# mippe_32u4.net
KiCad netlist of a schematic drawn in EAGLE
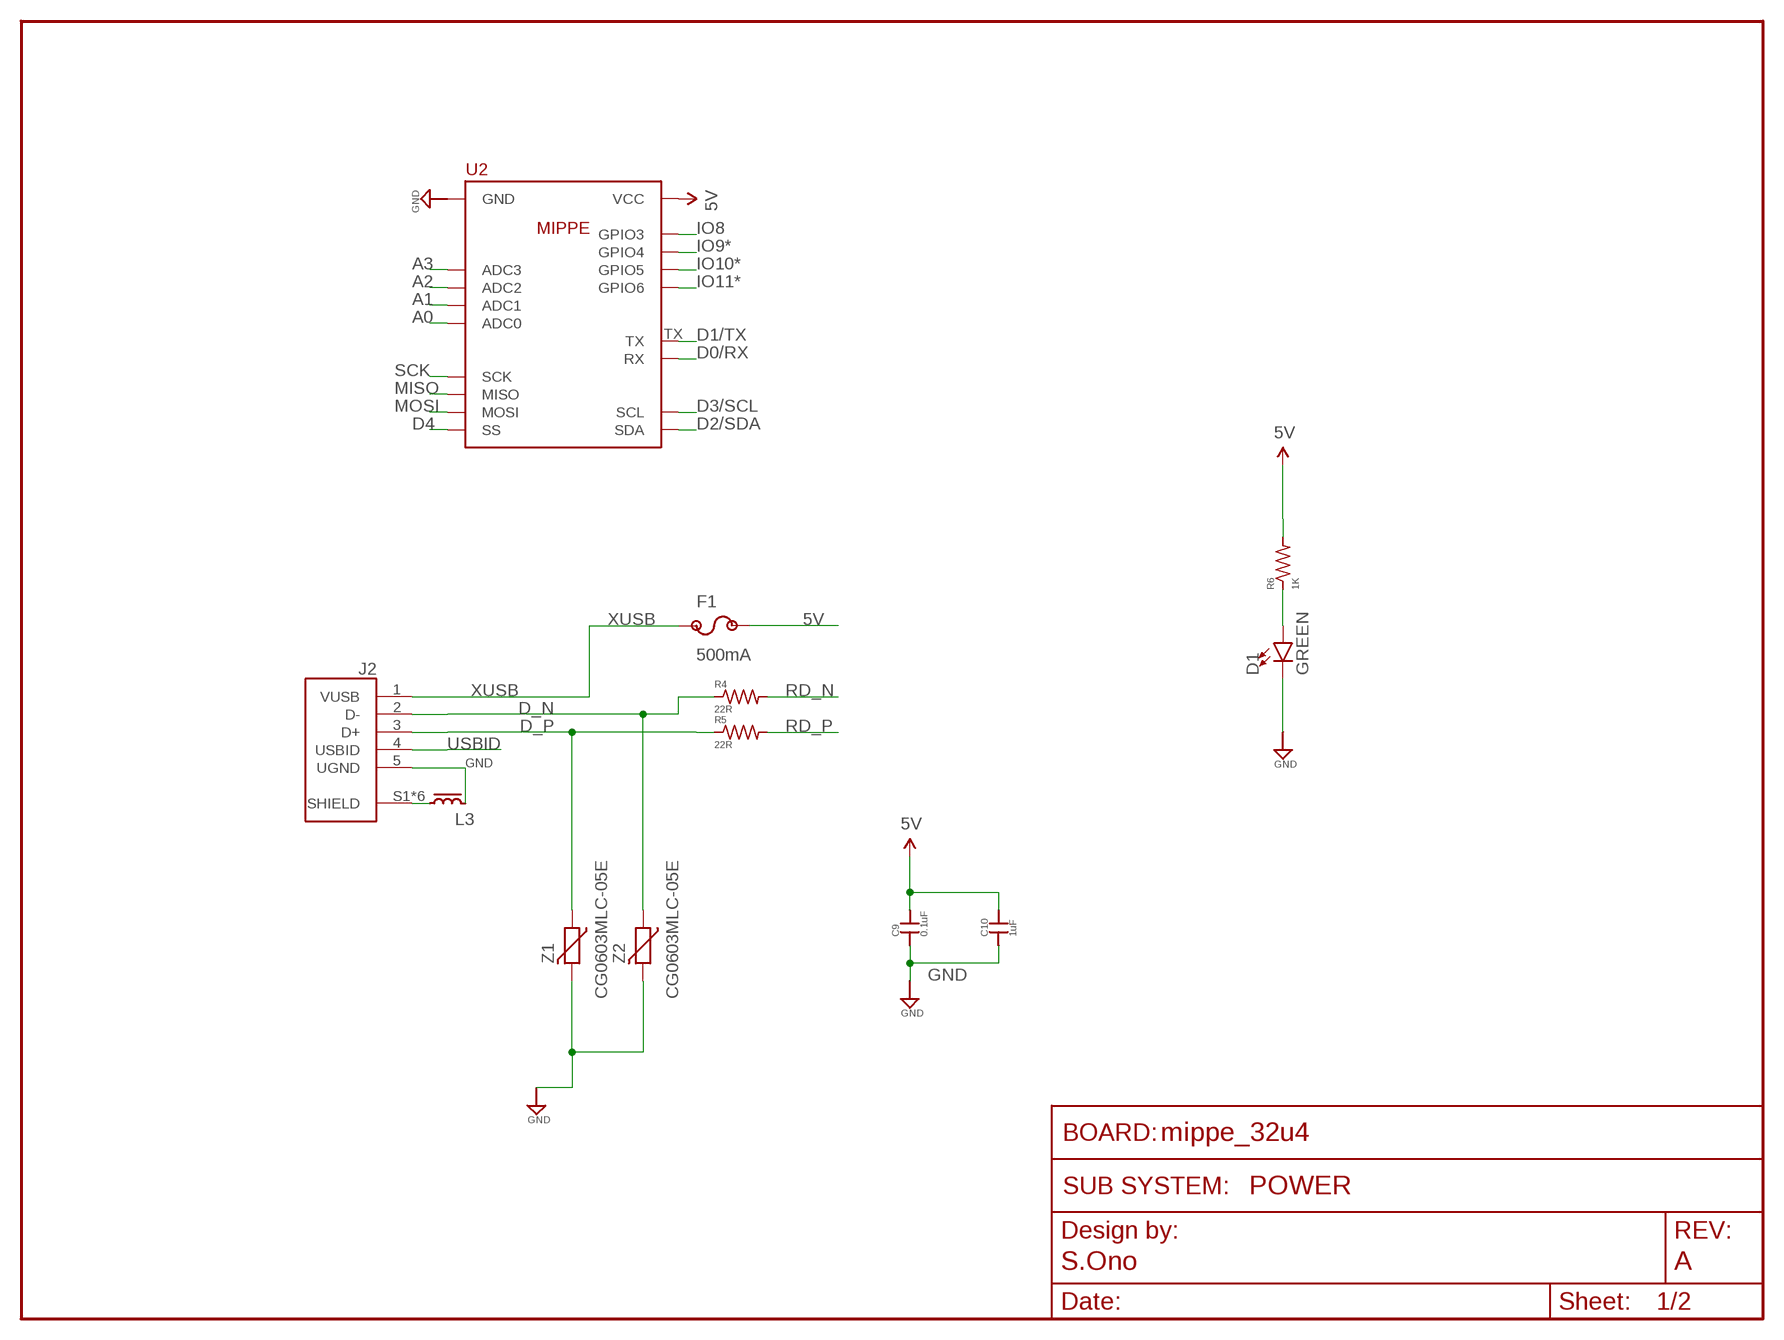
[diagram p0: schematic, sheet 1]
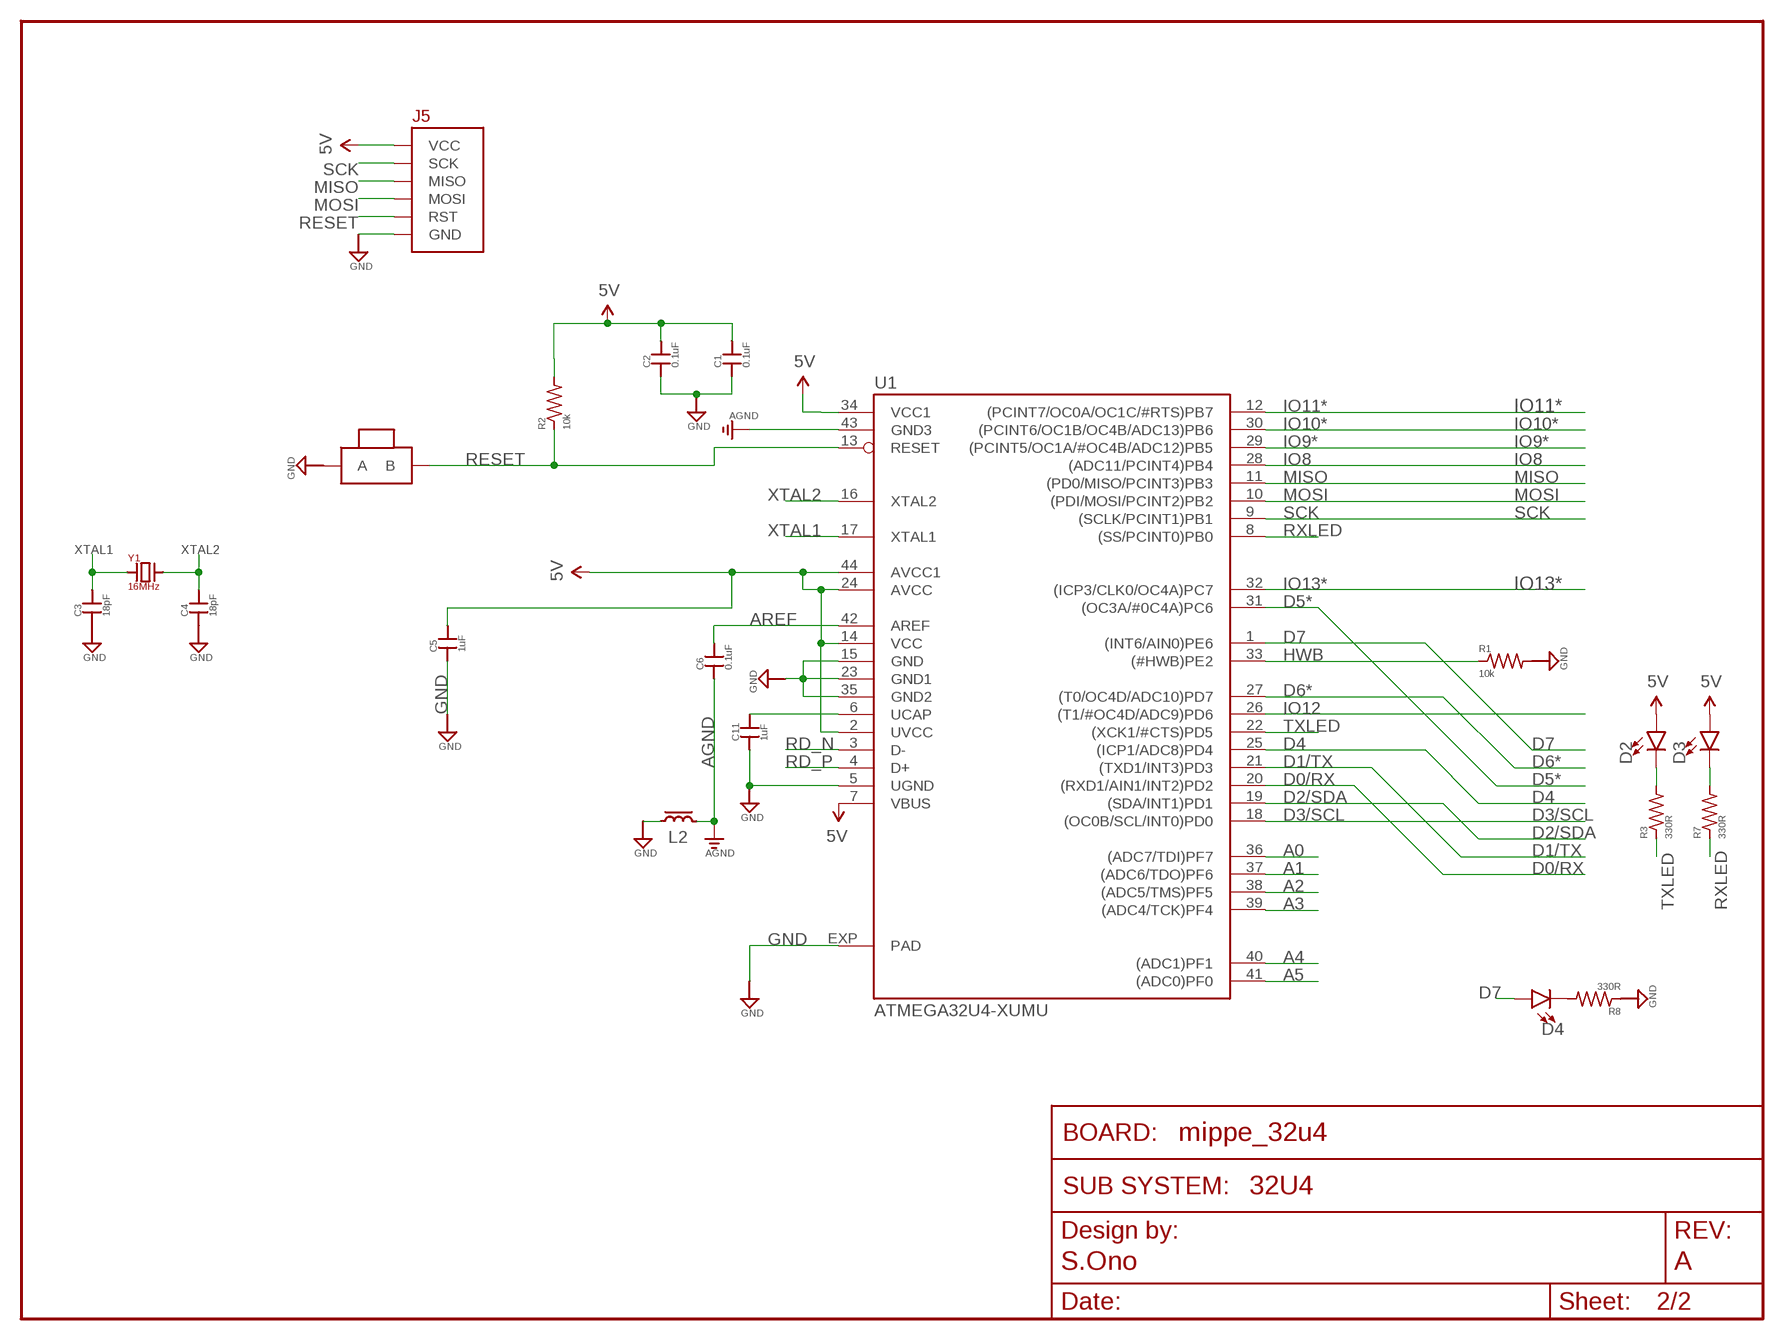
[diagram p1: schematic, sheet 2]

(export (version "E")
  (design (tool "Eeschema 10.0.6"))
  (components
    (comp (ref "C9")
      (value "0.1uF")
      (footprint "eagle-import:0603-CAP")
      (libsource (lib "eagle-import") (part "CAP0603-CAP"))
    )
    (comp (ref "C10")
      (value "1uF")
      (footprint "eagle-import:0603-CAP")
      (libsource (lib "eagle-import") (part "CAP0603-CAP"))
    )
    (comp (ref "D1")
      (value "GREEN")
      (footprint "eagle-import:LED-0603")
      (libsource (lib "eagle-import") (part "LED0603"))
    )
    (comp (ref "F1")
      (value "500mA")
      (footprint "eagle-import:1206")
      (libsource (lib "eagle-import") (part "0ZCJ0050FF2G1206"))
    )
    (comp (ref "J2")
      (value "USB")
      (footprint "eagle-import:FCI_10103594-0001LF")
      (fields
        (field (name "DIGI-KEY_PART_NUMBER") "609-4050-1-ND")
        (field (name "MF") "Amphenol ICC")
        (field (name "MP") "10103594-0001LF")
      )
      (libsource (lib "eagle-import") (part "USB"))
    )
    (comp (ref "L3")
      (value "IND")
      (footprint "eagle-import:IND_2012")
      (fields (field (name "MANUFACTURER_PART_NUMBER") "MLZ2012M1R0HT000"))
      (libsource (lib "eagle-import") (part "IND"))
    )
    (comp (ref "R4")
      (value "22R")
      (footprint "eagle-import:0603-RES")
      (libsource (lib "eagle-import") (part "R-US_0603"))
    )
    (comp (ref "R5")
      (value "22R")
      (footprint "eagle-import:0603-RES")
      (libsource (lib "eagle-import") (part "R-US_0603"))
    )
    (comp (ref "R6")
      (value "1K")
      (footprint "eagle-import:0603-RES")
      (libsource (lib "eagle-import") (part "R-US_0603"))
    )
    (comp (ref "U2")
      (value "MIPPE")
      (footprint "eagle-import:MIPPE")
      (libsource (lib "eagle-import") (part "MIPPE"))
    )
    (comp (ref "Z1")
      (value "CG0603MLC-05E")
      (footprint "eagle-import:0603-RES")
      (libsource (lib "eagle-import") (part "VARISTOR"))
    )
    (comp (ref "Z2")
      (value "CG0603MLC-05E")
      (footprint "eagle-import:0603-RES")
      (libsource (lib "eagle-import") (part "VARISTOR"))
    )
    (comp (ref "C1")
      (value "0.1uF")
      (footprint "eagle-import:0603-CAP")
      (libsource (lib "eagle-import") (part "CAP0603-CAP"))
    )
    (comp (ref "C2")
      (value "0.1uF")
      (footprint "eagle-import:0603-CAP")
      (libsource (lib "eagle-import") (part "CAP0603-CAP"))
    )
    (comp (ref "C3")
      (value "18pF")
      (footprint "eagle-import:0603-CAP")
      (libsource (lib "eagle-import") (part "CAP0603-CAP"))
    )
    (comp (ref "C4")
      (value "18pF")
      (footprint "eagle-import:0603-CAP")
      (libsource (lib "eagle-import") (part "CAP0603-CAP"))
    )
    (comp (ref "C5")
      (value "1uF")
      (footprint "eagle-import:0603-CAP")
      (libsource (lib "eagle-import") (part "CAP0603-CAP"))
    )
    (comp (ref "C6")
      (value "0.1uF")
      (footprint "eagle-import:0603-CAP")
      (libsource (lib "eagle-import") (part "CAP0603-CAP"))
    )
    (comp (ref "C11")
      (value "1uF")
      (footprint "eagle-import:0603-CAP")
      (libsource (lib "eagle-import") (part "CAP0603-CAP"))
    )
    (comp (ref "D2")
      (value "LED0603")
      (footprint "eagle-import:LED-0603")
      (libsource (lib "eagle-import") (part "LED0603"))
    )
    (comp (ref "D3")
      (value "LED0603")
      (footprint "eagle-import:LED-0603")
      (libsource (lib "eagle-import") (part "LED0603"))
    )
    (comp (ref "D4")
      (value "LED0603")
      (footprint "eagle-import:LED-0603")
      (libsource (lib "eagle-import") (part "LED0603"))
    )
    (comp (ref "J5")
      (value "BURNIN")
      (footprint "eagle-import:BURNIN")
      (libsource (lib "eagle-import") (part "BURNIN"))
    )
    (comp (ref "L2")
      (value "IND")
      (footprint "eagle-import:IND_2012")
      (fields (field (name "MANUFACTURER_PART_NUMBER") "MLZ2012M1R0HT000"))
      (libsource (lib "eagle-import") (part "IND"))
    )
    (comp (ref "R1")
      (value "10k")
      (footprint "eagle-import:0603-RES")
      (libsource (lib "eagle-import") (part "R-US_0603"))
    )
    (comp (ref "R2")
      (value "10k")
      (footprint "eagle-import:0603-RES")
      (libsource (lib "eagle-import") (part "R-US_0603"))
    )
    (comp (ref "R3")
      (value "330R")
      (footprint "eagle-import:0603-RES")
      (libsource (lib "eagle-import") (part "R-US_0603"))
    )
    (comp (ref "R7")
      (value "330R")
      (footprint "eagle-import:0603-RES")
      (libsource (lib "eagle-import") (part "R-US_0603"))
    )
    (comp (ref "R8")
      (value "330R")
      (footprint "eagle-import:0603-RES")
      (libsource (lib "eagle-import") (part "R-US_0603"))
    )
    (comp (ref "SW1")
      (value "BTN-PTS810")
      (footprint "eagle-import:BTN_PTS810")
      (libsource (lib "eagle-import") (part "BTN-PTS810"))
    )
    (comp (ref "U1")
      (value "ATMEGA32U4-XUMU")
      (footprint "eagle-import:QFN44ML7X7")
      (libsource (lib "eagle-import") (part "ATMEGA32U4-XUMU"))
    )
    (comp (ref "Y1")
      (value "16MHz")
      (footprint "eagle-import:XTAL500X320X130N")
      (libsource (lib "eagle-import") (part "CRYSTAL_SMOL"))
    )
  )
  (nets
    (net (code "1") (name "5V") (class "Default")
      (node (ref "C1") (pin "2") (pinfunction "2_2") (pintype "passive"))
      (node (ref "C10") (pin "2") (pinfunction "2_2") (pintype "passive"))
      (node (ref "C2") (pin "2") (pinfunction "2_2") (pintype "passive"))
      (node (ref "C5") (pin "2") (pinfunction "2_2") (pintype "passive"))
      (node (ref "C9") (pin "2") (pinfunction "2_2") (pintype "passive"))
      (node (ref "D2") (pin "A") (pinfunction "A_A") (pintype "passive"))
      (node (ref "D3") (pin "A") (pinfunction "A_A") (pintype "passive"))
      (node (ref "F1") (pin "2") (pinfunction "2_2") (pintype "passive"))
      (node (ref "J5") (pin "3.3V") (pinfunction "VCC_3.3V") (pintype "power_in"))
      (node (ref "R2") (pin "2") (pinfunction "2_2") (pintype "passive"))
      (node (ref "R6") (pin "2") (pinfunction "2_2") (pintype "passive"))
      (node (ref "U1") (pin "14") (pinfunction "VCC_14") (pintype "power_in"))
      (node (ref "U1") (pin "2") (pinfunction "UVCC_2") (pintype "power_in"))
      (node (ref "U1") (pin "24") (pinfunction "AVCC_24") (pintype "power_in"))
      (node (ref "U1") (pin "34") (pinfunction "VCC1_34") (pintype "power_in"))
      (node (ref "U1") (pin "44") (pinfunction "AVCC1_44") (pintype "power_in"))
      (node (ref "U1") (pin "7") (pinfunction "VBUS_7") (pintype "input"))
      (node (ref "U2") (pin "VCC") (pinfunction "VCC_VCC") (pintype "power_in"))
      (node (ref "U2") (pin "VCC@1") (pinfunction "VCC_VCC@1") (pintype "power_in"))
    )
    (net (code "2") (name "A0") (class "Default")
      (node (ref "U1") (pin "36") (pinfunction "(ADC7/TDI)PF7_36") (pintype "bidirectional"))
      (node (ref "U2") (pin "ADC0") (pinfunction "ADC0_ADC0") (pintype "bidirectional"))
    )
    (net (code "3") (name "A1") (class "Default")
      (node (ref "U1") (pin "37") (pinfunction "(ADC6/TDO)PF6_37") (pintype "bidirectional"))
      (node (ref "U2") (pin "ADC1") (pinfunction "ADC1_ADC1") (pintype "bidirectional"))
    )
    (net (code "4") (name "A2") (class "Default")
      (node (ref "U1") (pin "38") (pinfunction "(ADC5/TMS)PF5_38") (pintype "bidirectional"))
      (node (ref "U2") (pin "ADC2") (pinfunction "ADC2_ADC2") (pintype "bidirectional"))
    )
    (net (code "5") (name "A3") (class "Default")
      (node (ref "U1") (pin "39") (pinfunction "(ADC4/TCK)PF4_39") (pintype "bidirectional"))
      (node (ref "U2") (pin "ADC3") (pinfunction "ADC3_ADC3") (pintype "bidirectional"))
    )
    (net (code "6") (name "A4") (class "Default")
      (node (ref "U1") (pin "40") (pinfunction "(ADC1)PF1_40") (pintype "bidirectional"))
    )
    (net (code "7") (name "A5") (class "Default")
      (node (ref "U1") (pin "41") (pinfunction "(ADC0)PF0_41") (pintype "bidirectional"))
    )
    (net (code "8") (name "AGND") (class "Default")
      (node (ref "C6") (pin "1") (pinfunction "1_1") (pintype "passive"))
      (node (ref "L2") (pin "2") (pinfunction "P$2_2") (pintype "passive"))
      (node (ref "U1") (pin "43") (pinfunction "GND3_43") (pintype "power_in"))
    )
    (net (code "9") (name "AREF") (class "Default")
      (node (ref "C6") (pin "2") (pinfunction "2_2") (pintype "passive"))
      (node (ref "U1") (pin "42") (pinfunction "AREF_42") (pintype "power_in"))
    )
    (net (code "10") (name "D0{slash}RX") (class "Default")
      (node (ref "U1") (pin "20") (pinfunction "(RXD1/AIN1/INT2)PD2_20") (pintype "bidirectional"))
      (node (ref "U2") (pin "RX") (pinfunction "RX_RX") (pintype "bidirectional"))
    )
    (net (code "11") (name "D1{slash}TX") (class "Default")
      (node (ref "U1") (pin "21") (pinfunction "(TXD1/INT3)PD3_21") (pintype "bidirectional"))
      (node (ref "U2") (pin "TX") (pinfunction "TX_TX") (pintype "bidirectional"))
    )
    (net (code "12") (name "D2{slash}SDA") (class "Default")
      (node (ref "U1") (pin "19") (pinfunction "(SDA/INT1)PD1_19") (pintype "bidirectional"))
      (node (ref "U2") (pin "SDA") (pinfunction "SDA_SDA") (pintype "bidirectional"))
    )
    (net (code "13") (name "D3{slash}SCL") (class "Default")
      (node (ref "U1") (pin "18") (pinfunction "(OC0B/SCL/INT0)PD0_18") (pintype "bidirectional"))
      (node (ref "U2") (pin "SCL") (pinfunction "SCL_SCL") (pintype "bidirectional"))
    )
    (net (code "14") (name "D4") (class "Default")
      (node (ref "U1") (pin "25") (pinfunction "(ICP1/ADC8)PD4_25") (pintype "bidirectional"))
      (node (ref "U2") (pin "SS") (pinfunction "SS_SS") (pintype "bidirectional"))
    )
    (net (code "15") (name "D5*") (class "Default")
      (node (ref "U1") (pin "31") (pinfunction "(OC3A/#0C4A)PC6_31") (pintype "bidirectional"))
    )
    (net (code "16") (name "D6*") (class "Default")
      (node (ref "U1") (pin "27") (pinfunction "(T0/OC4D/ADC10)PD7_27") (pintype "bidirectional"))
    )
    (net (code "17") (name "D7") (class "Default")
      (node (ref "D4") (pin "A") (pinfunction "A_A") (pintype "passive"))
      (node (ref "U1") (pin "1") (pinfunction "(INT6/AIN0)PE6_1") (pintype "bidirectional"))
    )
    (net (code "18") (name "D_N") (class "Default")
      (node (ref "J2") (pin "2") (pinfunction "D-_2") (pintype "passive"))
      (node (ref "R4") (pin "1") (pinfunction "1_1") (pintype "passive"))
      (node (ref "Z2") (pin "1") (pinfunction "1_1") (pintype "passive"))
    )
    (net (code "19") (name "D_P") (class "Default")
      (node (ref "J2") (pin "3") (pinfunction "D+_3") (pintype "passive"))
      (node (ref "R5") (pin "1") (pinfunction "1_1") (pintype "passive"))
      (node (ref "Z1") (pin "1") (pinfunction "1_1") (pintype "passive"))
    )
    (net (code "20") (name "GND") (class "Default")
      (node (ref "C1") (pin "1") (pinfunction "1_1") (pintype "passive"))
      (node (ref "C10") (pin "1") (pinfunction "1_1") (pintype "passive"))
      (node (ref "C11") (pin "1") (pinfunction "1_1") (pintype "passive"))
      (node (ref "C2") (pin "1") (pinfunction "1_1") (pintype "passive"))
      (node (ref "C3") (pin "1") (pinfunction "1_1") (pintype "passive"))
      (node (ref "C4") (pin "1") (pinfunction "1_1") (pintype "passive"))
      (node (ref "C5") (pin "1") (pinfunction "1_1") (pintype "passive"))
      (node (ref "C9") (pin "1") (pinfunction "1_1") (pintype "passive"))
      (node (ref "D1") (pin "C") (pinfunction "C_C") (pintype "passive"))
      (node (ref "J2") (pin "5") (pinfunction "UGND_5") (pintype "passive"))
      (node (ref "J5") (pin "GND") (pinfunction "GND_GND") (pintype "power_in"))
      (node (ref "L2") (pin "1") (pinfunction "P$1_1") (pintype "passive"))
      (node (ref "L3") (pin "2") (pinfunction "P$2_2") (pintype "passive"))
      (node (ref "R1") (pin "2") (pinfunction "2_2") (pintype "passive"))
      (node (ref "R8") (pin "1") (pinfunction "1_1") (pintype "passive"))
      (node (ref "SW1") (pin "1") (pinfunction "A_1") (pintype "bidirectional"))
      (node (ref "SW1") (pin "2") (pinfunction "A_2") (pintype "bidirectional"))
      (node (ref "U1") (pin "15") (pinfunction "GND_15") (pintype "power_in"))
      (node (ref "U1") (pin "23") (pinfunction "GND1_23") (pintype "power_in"))
      (node (ref "U1") (pin "35") (pinfunction "GND2_35") (pintype "power_in"))
      (node (ref "U1") (pin "5") (pinfunction "UGND_5") (pintype "power_in"))
      (node (ref "U1") (pin "EXP") (pinfunction "PAD_EXP") (pintype "power_in"))
      (node (ref "U2") (pin "GND@0") (pinfunction "GND_GND@0") (pintype "power_in"))
      (node (ref "U2") (pin "GND@1") (pinfunction "GND_GND@1") (pintype "power_in"))
      (node (ref "Z1") (pin "2") (pinfunction "2_2") (pintype "passive"))
      (node (ref "Z2") (pin "2") (pinfunction "2_2") (pintype "passive"))
    )
    (net (code "21") (name "HWB") (class "Default")
      (node (ref "R1") (pin "1") (pinfunction "1_1") (pintype "passive"))
      (node (ref "U1") (pin "33") (pinfunction "(#HWB)PE2_33") (pintype "bidirectional"))
    )
    (net (code "22") (name "IO8") (class "Default")
      (node (ref "U1") (pin "28") (pinfunction "(ADC11/PCINT4)PB4_28") (pintype "bidirectional"))
      (node (ref "U2") (pin "GPIO3") (pinfunction "GPIO3_GPIO3") (pintype "bidirectional"))
    )
    (net (code "23") (name "IO9*") (class "Default")
      (node (ref "U1") (pin "29") (pinfunction "(PCINT5/OC1A/#OC4B/ADC12)PB5_29") (pintype "bidirectional"))
      (node (ref "U2") (pin "GPIO4") (pinfunction "GPIO4_GPIO4") (pintype "bidirectional"))
    )
    (net (code "24") (name "IO10*") (class "Default")
      (node (ref "U1") (pin "30") (pinfunction "(PCINT6/OC1B/OC4B/ADC13)PB6_30") (pintype "bidirectional"))
      (node (ref "U2") (pin "GPIO5") (pinfunction "GPIO5_GPIO5") (pintype "bidirectional"))
    )
    (net (code "25") (name "IO11*") (class "Default")
      (node (ref "U1") (pin "12") (pinfunction "(PCINT7/OC0A/OC1C/#RTS)PB7_12") (pintype "bidirectional"))
      (node (ref "U2") (pin "GPIO6") (pinfunction "GPIO6_GPIO6") (pintype "bidirectional"))
    )
    (net (code "26") (name "IO12") (class "Default")
      (node (ref "U1") (pin "26") (pinfunction "(T1/#OC4D/ADC9)PD6_26") (pintype "bidirectional"))
    )
    (net (code "27") (name "IO13*") (class "Default")
      (node (ref "U1") (pin "32") (pinfunction "(ICP3/CLK0/OC4A)PC7_32") (pintype "bidirectional"))
    )
    (net (code "28") (name "MISO") (class "Default")
      (node (ref "J5") (pin "MISO") (pinfunction "MISO_MISO") (pintype "bidirectional"))
      (node (ref "U1") (pin "11") (pinfunction "(PD0/MISO/PCINT3)PB3_11") (pintype "bidirectional"))
      (node (ref "U2") (pin "MISO") (pinfunction "MISO_MISO") (pintype "bidirectional"))
    )
    (net (code "29") (name "MOSI") (class "Default")
      (node (ref "J5") (pin "MOSI") (pinfunction "MOSI_MOSI") (pintype "bidirectional"))
      (node (ref "U1") (pin "10") (pinfunction "(PDI/MOSI/PCINT2)PB2_10") (pintype "bidirectional"))
      (node (ref "U2") (pin "MOSI") (pinfunction "MOSI_MOSI") (pintype "bidirectional"))
    )
    (net (code "30") (name "Net-(D1-PadA)") (class "Default")
      (node (ref "D1") (pin "A") (pinfunction "A_A") (pintype "passive"))
      (node (ref "R6") (pin "1") (pinfunction "1_1") (pintype "passive"))
    )
    (net (code "31") (name "Net-(D2-PadC)") (class "Default")
      (node (ref "D2") (pin "C") (pinfunction "C_C") (pintype "passive"))
      (node (ref "R3") (pin "2") (pinfunction "2_2") (pintype "passive"))
    )
    (net (code "32") (name "Net-(D3-PadC)") (class "Default")
      (node (ref "D3") (pin "C") (pinfunction "C_C") (pintype "passive"))
      (node (ref "R7") (pin "2") (pinfunction "2_2") (pintype "passive"))
    )
    (net (code "33") (name "Net-(D4-PadC)") (class "Default")
      (node (ref "D4") (pin "C") (pinfunction "C_C") (pintype "passive"))
      (node (ref "R8") (pin "2") (pinfunction "2_2") (pintype "passive"))
    )
    (net (code "34") (name "Net-(L3-P$1)") (class "Default")
      (node (ref "J2") (pin "S1") (pinfunction "SHIELD_S1") (pintype "passive"))
      (node (ref "J2") (pin "S2") (pinfunction "SHIELD_S2") (pintype "passive"))
      (node (ref "J2") (pin "S3") (pinfunction "SHIELD_S3") (pintype "passive"))
      (node (ref "J2") (pin "S4") (pinfunction "SHIELD_S4") (pintype "passive"))
      (node (ref "J2") (pin "S5") (pinfunction "SHIELD_S5") (pintype "passive"))
      (node (ref "J2") (pin "S6") (pinfunction "SHIELD_S6") (pintype "passive"))
      (node (ref "L3") (pin "1") (pinfunction "P$1_1") (pintype "passive"))
    )
    (net (code "35") (name "Net-(U1-UCAP)") (class "Default")
      (node (ref "C11") (pin "2") (pinfunction "2_2") (pintype "passive"))
      (node (ref "U1") (pin "6") (pinfunction "UCAP_6") (pintype "passive"))
    )
    (net (code "36") (name "RD_N") (class "Default")
      (node (ref "R4") (pin "2") (pinfunction "2_2") (pintype "passive"))
      (node (ref "U1") (pin "3") (pinfunction "D-_3") (pintype "bidirectional"))
    )
    (net (code "37") (name "RD_P") (class "Default")
      (node (ref "R5") (pin "2") (pinfunction "2_2") (pintype "passive"))
      (node (ref "U1") (pin "4") (pinfunction "D+_4") (pintype "bidirectional"))
    )
    (net (code "38") (name "RESET") (class "Default")
      (node (ref "J5") (pin "RST") (pinfunction "RST_RST") (pintype "bidirectional"))
      (node (ref "R2") (pin "1") (pinfunction "1_1") (pintype "passive"))
      (node (ref "SW1") (pin "3") (pinfunction "B_3") (pintype "bidirectional"))
      (node (ref "SW1") (pin "4") (pinfunction "B_4") (pintype "bidirectional"))
      (node (ref "U1") (pin "13") (pinfunction "RESET_13") (pintype "input"))
    )
    (net (code "39") (name "RXLED") (class "Default")
      (node (ref "R7") (pin "1") (pinfunction "1_1") (pintype "passive"))
      (node (ref "U1") (pin "8") (pinfunction "(SS/PCINT0)PB0_8") (pintype "bidirectional"))
    )
    (net (code "40") (name "SCK") (class "Default")
      (node (ref "J5") (pin "SCK") (pinfunction "SCK_SCK") (pintype "bidirectional"))
      (node (ref "U1") (pin "9") (pinfunction "(SCLK/PCINT1)PB1_9") (pintype "bidirectional"))
      (node (ref "U2") (pin "SCK") (pinfunction "SCK_SCK") (pintype "bidirectional"))
    )
    (net (code "41") (name "TXLED") (class "Default")
      (node (ref "R3") (pin "1") (pinfunction "1_1") (pintype "passive"))
      (node (ref "U1") (pin "22") (pinfunction "(XCK1/#CTS)PD5_22") (pintype "bidirectional"))
    )
    (net (code "42") (name "USBID") (class "Default")
      (node (ref "J2") (pin "4") (pinfunction "USBID_4") (pintype "passive"))
    )
    (net (code "43") (name "XTAL1") (class "Default")
      (node (ref "C3") (pin "2") (pinfunction "2_2") (pintype "passive"))
      (node (ref "U1") (pin "17") (pinfunction "XTAL1_17") (pintype "bidirectional"))
      (node (ref "Y1") (pin "1") (pinfunction "A_1") (pintype "passive"))
    )
    (net (code "44") (name "XTAL2") (class "Default")
      (node (ref "C4") (pin "2") (pinfunction "2_2") (pintype "passive"))
      (node (ref "U1") (pin "16") (pinfunction "XTAL2_16") (pintype "bidirectional"))
      (node (ref "Y1") (pin "2") (pinfunction "B_2") (pintype "passive"))
    )
    (net (code "45") (name "XUSB") (class "Default")
      (node (ref "F1") (pin "1") (pinfunction "1_1") (pintype "passive"))
      (node (ref "J2") (pin "1") (pinfunction "VUSB_1") (pintype "passive"))
    )
  )
)
